# GAME.net
KiCad netlist of a schematic drawn in EAGLE
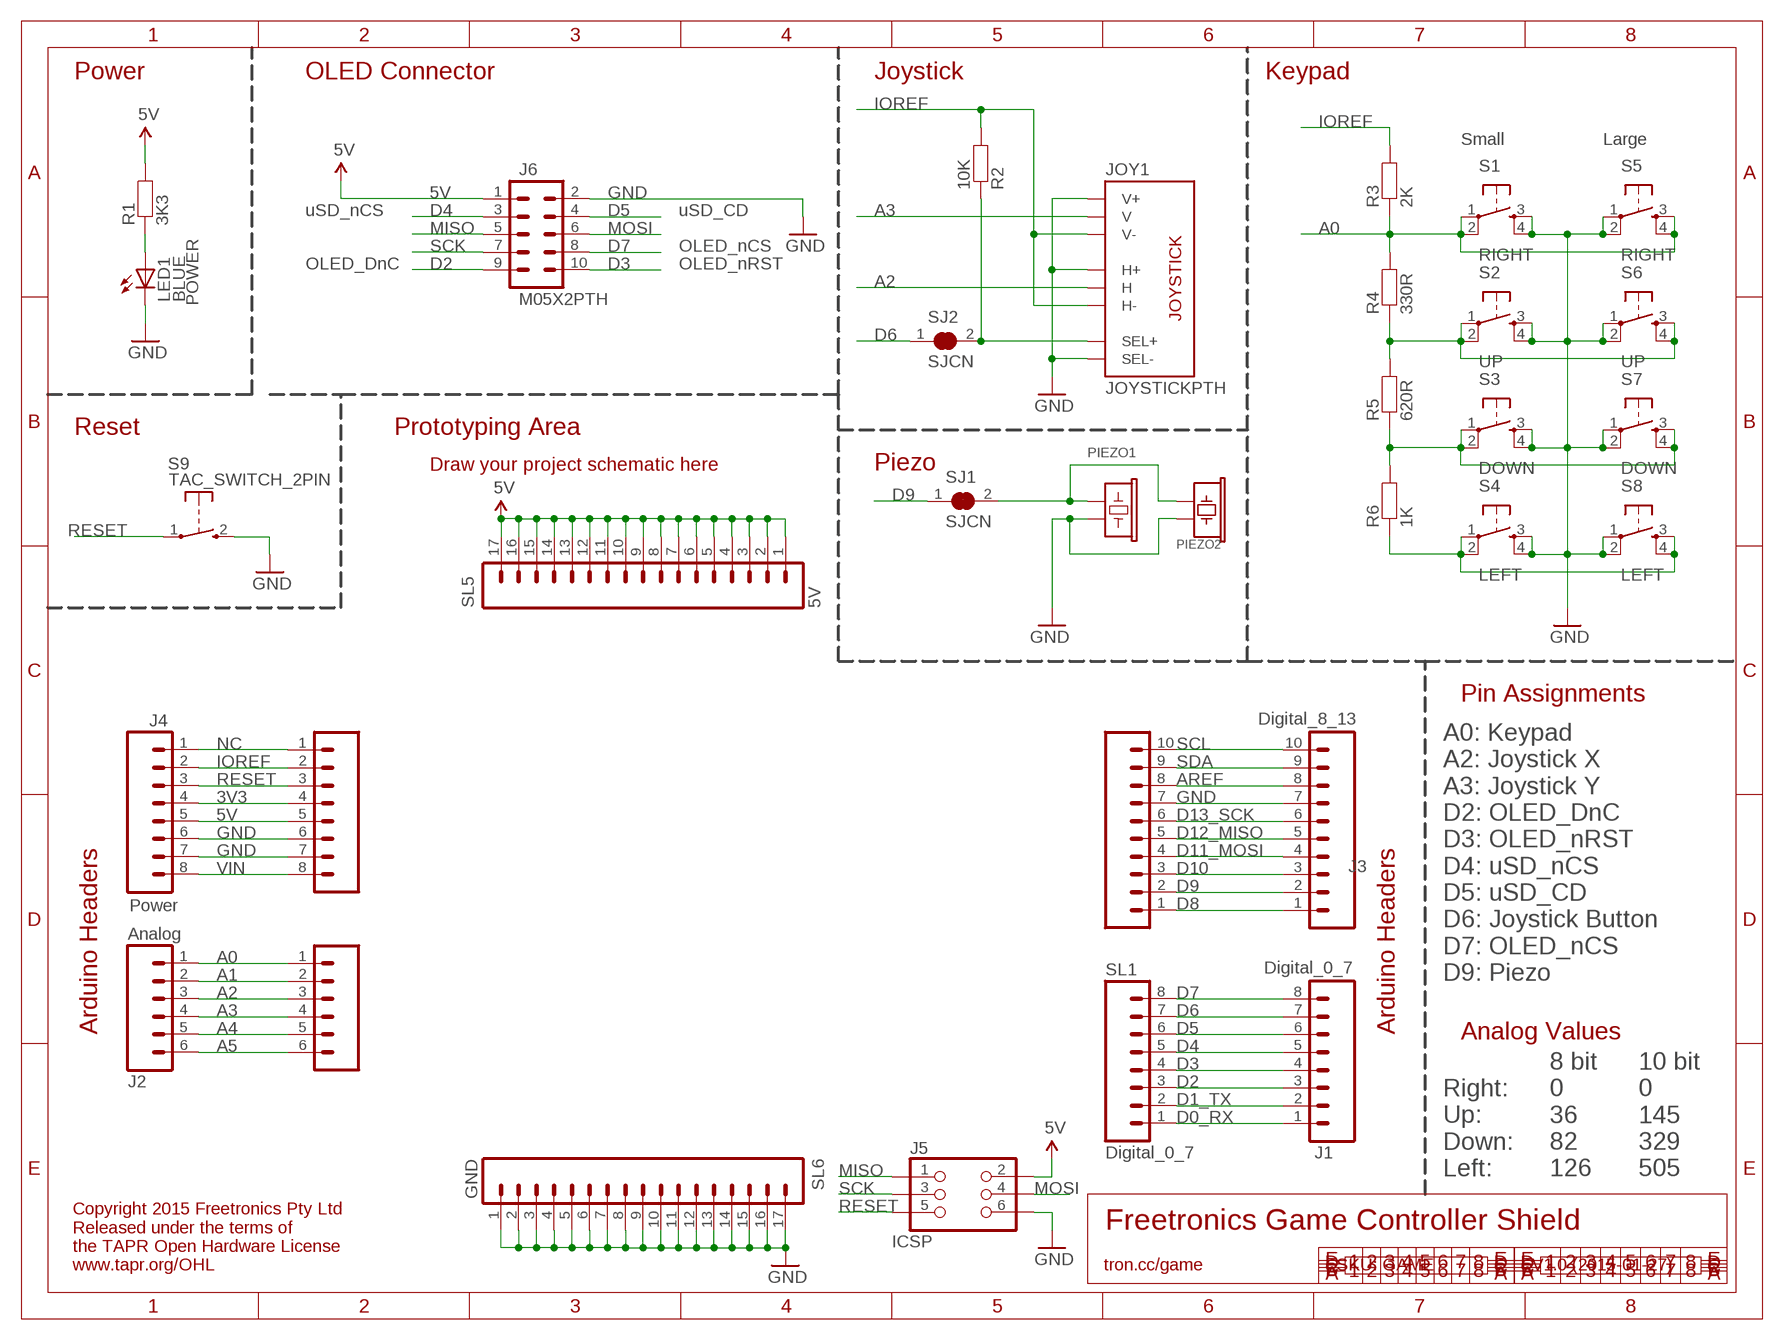
[diagram p0: schematic, sheet 1]

(export (version "E")
  (design (tool "Eeschema 10.0.6"))
  (components
    (comp (ref "J1")
      (value "Digital_0_7")
      (footprint "eagle-import:1X08")
      (libsource (lib "eagle-import") (part "M08"))
    )
    (comp (ref "J2")
      (value "Analog")
      (footprint "eagle-import:1X06")
      (libsource (lib "eagle-import") (part "M06SIP"))
    )
    (comp (ref "J3")
      (value "Digital_8_13")
      (footprint "eagle-import:1X10")
      (libsource (lib "eagle-import") (part "M100.1"))
    )
    (comp (ref "J4")
      (value "Power")
      (footprint "eagle-import:1X08")
      (libsource (lib "eagle-import") (part "M08"))
    )
    (comp (ref "J5")
      (value "ICSP")
      (footprint "eagle-import:2X03PTH")
      (libsource (lib "eagle-import") (part "ICSPPTH"))
    )
    (comp (ref "J6")
      (value "M05X2PTH")
      (footprint "eagle-import:AVR_ICSP")
      (libsource (lib "eagle-import") (part "M05X2PTH"))
    )
    (comp (ref "JOY1")
      (value "JOYSTICKPTH")
      (footprint "eagle-import:JOYSTICK")
      (libsource (lib "eagle-import") (part "JOYSTICKPTH"))
    )
    (comp (ref "LED1")
      (value "BLUE")
      (footprint "eagle-import:LED-0603")
      (libsource (lib "eagle-import") (part "LED0603"))
    )
    (comp (ref "PIEZO1")
      (value "BUZZERSMD12X12")
      (footprint "eagle-import:BUZZER-12X12-SMT")
      (libsource (lib "eagle-import") (part "BUZZERSMD12X12"))
    )
    (comp (ref "PIEZO2")
      (value "PIEZO12MM")
      (footprint "eagle-import:PIEZO12MM")
      (libsource (lib "eagle-import") (part "PIEZO12MM"))
    )
    (comp (ref "R1")
      (value "3K3")
      (footprint "eagle-import:0603")
      (libsource (lib "eagle-import") (part "RESISTOR0603"))
    )
    (comp (ref "R2")
      (value "10K")
      (footprint "eagle-import:0603")
      (libsource (lib "eagle-import") (part "RESISTOR0603"))
    )
    (comp (ref "R3")
      (value "2K")
      (footprint "eagle-import:0603")
      (libsource (lib "eagle-import") (part "RESISTOR0603"))
    )
    (comp (ref "R4")
      (value "330R")
      (footprint "eagle-import:0603")
      (libsource (lib "eagle-import") (part "RESISTOR0603"))
    )
    (comp (ref "R5")
      (value "620R")
      (footprint "eagle-import:0603")
      (libsource (lib "eagle-import") (part "RESISTOR0603"))
    )
    (comp (ref "R6")
      (value "1K")
      (footprint "eagle-import:0603")
      (libsource (lib "eagle-import") (part "RESISTOR0603"))
    )
    (comp (ref "S1")
      (value "RIGHT")
      (footprint "eagle-import:TACTILE-PTH")
      (libsource (lib "eagle-import") (part "TAC_SWITCHPTH"))
    )
    (comp (ref "S2")
      (value "UP")
      (footprint "eagle-import:TACTILE-PTH")
      (libsource (lib "eagle-import") (part "TAC_SWITCHPTH"))
    )
    (comp (ref "S3")
      (value "DOWN")
      (footprint "eagle-import:TACTILE-PTH")
      (libsource (lib "eagle-import") (part "TAC_SWITCHPTH"))
    )
    (comp (ref "S4")
      (value "LEFT")
      (footprint "eagle-import:TACTILE-PTH")
      (libsource (lib "eagle-import") (part "TAC_SWITCHPTH"))
    )
    (comp (ref "S5")
      (value "RIGHT")
      (footprint "eagle-import:TACTILE-PTH-12MM")
      (libsource (lib "eagle-import") (part "TAC_SWITCH12"))
    )
    (comp (ref "S6")
      (value "UP")
      (footprint "eagle-import:TACTILE-PTH-12MM")
      (libsource (lib "eagle-import") (part "TAC_SWITCH12"))
    )
    (comp (ref "S7")
      (value "DOWN")
      (footprint "eagle-import:TACTILE-PTH-12MM")
      (libsource (lib "eagle-import") (part "TAC_SWITCH12"))
    )
    (comp (ref "S8")
      (value "LEFT")
      (footprint "eagle-import:TACTILE-PTH-12MM")
      (libsource (lib "eagle-import") (part "TAC_SWITCH12"))
    )
    (comp (ref "S9")
      (value "TAC_SWITCH_2PIN")
      (footprint "eagle-import:TACTILE_SWITCH_SMD_2PIN_TINY")
      (libsource (lib "eagle-import") (part "TAC_SWITCH_2PIN"))
    )
    (comp (ref "SJ1")
      (value "SJCN")
      (footprint "eagle-import:SJC")
      (libsource (lib "eagle-import") (part "SJCN"))
    )
    (comp (ref "SJ2")
      (value "SJCN")
      (footprint "eagle-import:SJC")
      (libsource (lib "eagle-import") (part "SJCN"))
    )
    (comp (ref "SL1")
      (value "Digital_0_7")
      (footprint "eagle-import:1X08")
      (libsource (lib "eagle-import") (part "freetronics-original_M08"))
    )
    (comp (ref "SL2")
      (value "Analog")
      (footprint "eagle-import:1X06")
      (libsource (lib "eagle-import") (part "M06SIP"))
    )
    (comp (ref "SL3")
      (value "Digital_8_13")
      (footprint "eagle-import:1X10")
      (libsource (lib "eagle-import") (part "M100.1"))
    )
    (comp (ref "SL4")
      (value "Power")
      (footprint "eagle-import:1X08")
      (libsource (lib "eagle-import") (part "M08"))
    )
    (comp (ref "SL5")
      (value "5V")
      (footprint "eagle-import:1X17")
      (libsource (lib "eagle-import") (part "M17"))
    )
    (comp (ref "SL6")
      (value "GND")
      (footprint "eagle-import:1X17")
      (libsource (lib "eagle-import") (part "M17"))
    )
  )
  (nets
    (net (code "1") (name "/3V3") (class "Default")
      (node (ref "J4") (pin "4") (pinfunction "4_4") (pintype "passive"))
      (node (ref "SL4") (pin "4") (pinfunction "4_4") (pintype "passive"))
    )
    (net (code "2") (name "/A0") (class "Default")
      (node (ref "J2") (pin "1") (pinfunction "1_1") (pintype "passive"))
      (node (ref "R3") (pin "1") (pinfunction "1_1") (pintype "passive"))
      (node (ref "R4") (pin "2") (pinfunction "2_2") (pintype "passive"))
      (node (ref "S1") (pin "1") (pinfunction "1_1") (pintype "passive"))
      (node (ref "S1") (pin "2") (pinfunction "2_2") (pintype "passive"))
      (node (ref "S5") (pin "3") (pinfunction "3_3") (pintype "passive"))
      (node (ref "S5") (pin "4") (pinfunction "4_4") (pintype "passive"))
      (node (ref "SL2") (pin "1") (pinfunction "1_1") (pintype "passive"))
    )
    (net (code "3") (name "/A1") (class "Default")
      (node (ref "J2") (pin "2") (pinfunction "2_2") (pintype "passive"))
      (node (ref "SL2") (pin "2") (pinfunction "2_2") (pintype "passive"))
    )
    (net (code "4") (name "/A2") (class "Default")
      (node (ref "J2") (pin "3") (pinfunction "3_3") (pintype "passive"))
      (node (ref "JOY1") (pin "H2") (pinfunction "H_H2") (pintype "bidirectional"))
      (node (ref "SL2") (pin "3") (pinfunction "3_3") (pintype "passive"))
    )
    (net (code "5") (name "/A3") (class "Default")
      (node (ref "J2") (pin "4") (pinfunction "4_4") (pintype "passive"))
      (node (ref "JOY1") (pin "V2") (pinfunction "V_V2") (pintype "bidirectional"))
      (node (ref "SL2") (pin "4") (pinfunction "4_4") (pintype "passive"))
    )
    (net (code "6") (name "/A4") (class "Default")
      (node (ref "J2") (pin "5") (pinfunction "5_5") (pintype "passive"))
      (node (ref "SL2") (pin "5") (pinfunction "5_5") (pintype "passive"))
    )
    (net (code "7") (name "/A5") (class "Default")
      (node (ref "J2") (pin "6") (pinfunction "6_6") (pintype "passive"))
      (node (ref "SL2") (pin "6") (pinfunction "6_6") (pintype "passive"))
    )
    (net (code "8") (name "/AREF") (class "Default")
      (node (ref "J3") (pin "8") (pinfunction "8_8") (pintype "passive"))
      (node (ref "SL3") (pin "8") (pinfunction "8_8") (pintype "passive"))
    )
    (net (code "9") (name "/D0_RX") (class "Default")
      (node (ref "J1") (pin "1") (pinfunction "1_1") (pintype "passive"))
      (node (ref "SL1") (pin "1") (pinfunction "1_1") (pintype "passive"))
    )
    (net (code "10") (name "/D1_TX") (class "Default")
      (node (ref "J1") (pin "2") (pinfunction "2_2") (pintype "passive"))
      (node (ref "SL1") (pin "2") (pinfunction "2_2") (pintype "passive"))
    )
    (net (code "11") (name "/D2") (class "Default")
      (node (ref "J1") (pin "3") (pinfunction "3_3") (pintype "passive"))
      (node (ref "J6") (pin "9") (pinfunction "9_9") (pintype "passive"))
      (node (ref "SL1") (pin "3") (pinfunction "3_3") (pintype "passive"))
    )
    (net (code "12") (name "/D3") (class "Default")
      (node (ref "J1") (pin "4") (pinfunction "4_4") (pintype "passive"))
      (node (ref "J6") (pin "10") (pinfunction "10_10") (pintype "passive"))
      (node (ref "SL1") (pin "4") (pinfunction "4_4") (pintype "passive"))
    )
    (net (code "13") (name "/D4") (class "Default")
      (node (ref "J1") (pin "5") (pinfunction "5_5") (pintype "passive"))
      (node (ref "J6") (pin "3") (pinfunction "3_3") (pintype "passive"))
      (node (ref "SL1") (pin "5") (pinfunction "5_5") (pintype "passive"))
    )
    (net (code "14") (name "/D5") (class "Default")
      (node (ref "J1") (pin "6") (pinfunction "6_6") (pintype "passive"))
      (node (ref "J6") (pin "4") (pinfunction "4_4") (pintype "passive"))
      (node (ref "SL1") (pin "6") (pinfunction "6_6") (pintype "passive"))
    )
    (net (code "15") (name "/D6") (class "Default")
      (node (ref "J1") (pin "7") (pinfunction "7_7") (pintype "passive"))
      (node (ref "SJ2") (pin "1") (pinfunction "1_1") (pintype "passive"))
      (node (ref "SL1") (pin "7") (pinfunction "7_7") (pintype "passive"))
    )
    (net (code "16") (name "/D7") (class "Default")
      (node (ref "J1") (pin "8") (pinfunction "8_8") (pintype "passive"))
      (node (ref "J6") (pin "8") (pinfunction "8_8") (pintype "passive"))
      (node (ref "SL1") (pin "8") (pinfunction "8_8") (pintype "passive"))
    )
    (net (code "17") (name "/D8") (class "Default")
      (node (ref "J3") (pin "1") (pinfunction "1_1") (pintype "passive"))
      (node (ref "SL3") (pin "1") (pinfunction "1_1") (pintype "passive"))
    )
    (net (code "18") (name "/D9") (class "Default")
      (node (ref "J3") (pin "2") (pinfunction "2_2") (pintype "passive"))
      (node (ref "SJ1") (pin "1") (pinfunction "1_1") (pintype "passive"))
      (node (ref "SL3") (pin "2") (pinfunction "2_2") (pintype "passive"))
    )
    (net (code "19") (name "/D10") (class "Default")
      (node (ref "J3") (pin "3") (pinfunction "3_3") (pintype "passive"))
      (node (ref "SL3") (pin "3") (pinfunction "3_3") (pintype "passive"))
    )
    (net (code "20") (name "/D11_MOSI") (class "Default")
      (node (ref "J3") (pin "4") (pinfunction "4_4") (pintype "passive"))
      (node (ref "SL3") (pin "4") (pinfunction "4_4") (pintype "passive"))
    )
    (net (code "21") (name "/D12_MISO") (class "Default")
      (node (ref "J3") (pin "5") (pinfunction "5_5") (pintype "passive"))
      (node (ref "SL3") (pin "5") (pinfunction "5_5") (pintype "passive"))
    )
    (net (code "22") (name "/D13_SCK") (class "Default")
      (node (ref "J3") (pin "6") (pinfunction "6_6") (pintype "passive"))
      (node (ref "SL3") (pin "6") (pinfunction "6_6") (pintype "passive"))
    )
    (net (code "23") (name "/IOREF") (class "Default")
      (node (ref "J4") (pin "2") (pinfunction "2_2") (pintype "passive"))
      (node (ref "JOY1") (pin "H3") (pinfunction "H-_H3") (pintype "bidirectional"))
      (node (ref "JOY1") (pin "V3") (pinfunction "V-_V3") (pintype "bidirectional"))
      (node (ref "R2") (pin "2") (pinfunction "2_2") (pintype "passive"))
      (node (ref "R3") (pin "2") (pinfunction "2_2") (pintype "passive"))
      (node (ref "SL4") (pin "2") (pinfunction "2_2") (pintype "passive"))
    )
    (net (code "24") (name "/MISO") (class "Default")
      (node (ref "J5") (pin "1") (pinfunction "1_1") (pintype "passive"))
      (node (ref "J6") (pin "5") (pinfunction "5_5") (pintype "passive"))
    )
    (net (code "25") (name "/MOSI") (class "Default")
      (node (ref "J5") (pin "4") (pinfunction "4_4") (pintype "passive"))
      (node (ref "J6") (pin "6") (pinfunction "6_6") (pintype "passive"))
    )
    (net (code "26") (name "/NC") (class "Default")
      (node (ref "J4") (pin "1") (pinfunction "1_1") (pintype "passive"))
      (node (ref "SL4") (pin "1") (pinfunction "1_1") (pintype "passive"))
    )
    (net (code "27") (name "/RESET") (class "Default")
      (node (ref "J4") (pin "3") (pinfunction "3_3") (pintype "passive"))
      (node (ref "J5") (pin "5") (pinfunction "5_5") (pintype "passive"))
      (node (ref "S9") (pin "1") (pinfunction "P_1") (pintype "passive"))
      (node (ref "SL4") (pin "3") (pinfunction "3_3") (pintype "passive"))
    )
    (net (code "28") (name "/SCK") (class "Default")
      (node (ref "J5") (pin "3") (pinfunction "3_3") (pintype "passive"))
      (node (ref "J6") (pin "7") (pinfunction "7_7") (pintype "passive"))
    )
    (net (code "29") (name "/SCL") (class "Default")
      (node (ref "J3") (pin "10") (pinfunction "10_10") (pintype "passive"))
      (node (ref "SL3") (pin "10") (pinfunction "10_10") (pintype "passive"))
    )
    (net (code "30") (name "/SDA") (class "Default")
      (node (ref "J3") (pin "9") (pinfunction "9_9") (pintype "passive"))
      (node (ref "SL3") (pin "9") (pinfunction "9_9") (pintype "passive"))
    )
    (net (code "31") (name "/VIN") (class "Default")
      (node (ref "J4") (pin "8") (pinfunction "8_8") (pintype "passive"))
      (node (ref "SL4") (pin "8") (pinfunction "8_8") (pintype "passive"))
    )
    (net (code "32") (name "5V") (class "Default")
      (node (ref "J4") (pin "5") (pinfunction "5_5") (pintype "passive"))
      (node (ref "J5") (pin "2") (pinfunction "2_2") (pintype "passive"))
      (node (ref "J6") (pin "1") (pinfunction "1_1") (pintype "passive"))
      (node (ref "R1") (pin "2") (pinfunction "2_2") (pintype "passive"))
      (node (ref "SL4") (pin "5") (pinfunction "5_5") (pintype "passive"))
      (node (ref "SL5") (pin "1") (pinfunction "1_1") (pintype "passive"))
      (node (ref "SL5") (pin "10") (pinfunction "10_10") (pintype "passive"))
      (node (ref "SL5") (pin "11") (pinfunction "11_11") (pintype "passive"))
      (node (ref "SL5") (pin "12") (pinfunction "12_12") (pintype "passive"))
      (node (ref "SL5") (pin "13") (pinfunction "13_13") (pintype "passive"))
      (node (ref "SL5") (pin "14") (pinfunction "14_14") (pintype "passive"))
      (node (ref "SL5") (pin "15") (pinfunction "15_15") (pintype "passive"))
      (node (ref "SL5") (pin "16") (pinfunction "16_16") (pintype "passive"))
      (node (ref "SL5") (pin "17") (pinfunction "17_17") (pintype "passive"))
      (node (ref "SL5") (pin "2") (pinfunction "2_2") (pintype "passive"))
      (node (ref "SL5") (pin "3") (pinfunction "3_3") (pintype "passive"))
      (node (ref "SL5") (pin "4") (pinfunction "4_4") (pintype "passive"))
      (node (ref "SL5") (pin "5") (pinfunction "5_5") (pintype "passive"))
      (node (ref "SL5") (pin "6") (pinfunction "6_6") (pintype "passive"))
      (node (ref "SL5") (pin "7") (pinfunction "7_7") (pintype "passive"))
      (node (ref "SL5") (pin "8") (pinfunction "8_8") (pintype "passive"))
      (node (ref "SL5") (pin "9") (pinfunction "9_9") (pintype "passive"))
    )
    (net (code "33") (name "GND") (class "Default")
      (node (ref "J3") (pin "7") (pinfunction "7_7") (pintype "passive"))
      (node (ref "J4") (pin "6") (pinfunction "6_6") (pintype "passive"))
      (node (ref "J4") (pin "7") (pinfunction "7_7") (pintype "passive"))
      (node (ref "J5") (pin "6") (pinfunction "6_6") (pintype "passive"))
      (node (ref "J6") (pin "2") (pinfunction "2_2") (pintype "passive"))
      (node (ref "JOY1") (pin "B2A") (pinfunction "SEL-_B2A") (pintype "bidirectional"))
      (node (ref "JOY1") (pin "H1") (pinfunction "H+_H1") (pintype "bidirectional"))
      (node (ref "JOY1") (pin "V1") (pinfunction "V+_V1") (pintype "bidirectional"))
      (node (ref "LED1") (pin "C") (pinfunction "C_C") (pintype "passive"))
      (node (ref "PIEZO1") (pin "1") (pinfunction "1_1") (pintype "passive"))
      (node (ref "PIEZO2") (pin "2") (pinfunction "2_2") (pintype "bidirectional"))
      (node (ref "S1") (pin "3") (pinfunction "3_3") (pintype "passive"))
      (node (ref "S1") (pin "4") (pinfunction "4_4") (pintype "passive"))
      (node (ref "S2") (pin "3") (pinfunction "3_3") (pintype "passive"))
      (node (ref "S2") (pin "4") (pinfunction "4_4") (pintype "passive"))
      (node (ref "S3") (pin "3") (pinfunction "3_3") (pintype "passive"))
      (node (ref "S3") (pin "4") (pinfunction "4_4") (pintype "passive"))
      (node (ref "S4") (pin "3") (pinfunction "3_3") (pintype "passive"))
      (node (ref "S4") (pin "4") (pinfunction "4_4") (pintype "passive"))
      (node (ref "S5") (pin "1") (pinfunction "1_1") (pintype "passive"))
      (node (ref "S5") (pin "2") (pinfunction "2_2") (pintype "passive"))
      (node (ref "S6") (pin "1") (pinfunction "1_1") (pintype "passive"))
      (node (ref "S6") (pin "2") (pinfunction "2_2") (pintype "passive"))
      (node (ref "S7") (pin "1") (pinfunction "1_1") (pintype "passive"))
      (node (ref "S7") (pin "2") (pinfunction "2_2") (pintype "passive"))
      (node (ref "S8") (pin "1") (pinfunction "1_1") (pintype "passive"))
      (node (ref "S8") (pin "2") (pinfunction "2_2") (pintype "passive"))
      (node (ref "S9") (pin "2") (pinfunction "S_2") (pintype "passive"))
      (node (ref "SL3") (pin "7") (pinfunction "7_7") (pintype "passive"))
      (node (ref "SL4") (pin "6") (pinfunction "6_6") (pintype "passive"))
      (node (ref "SL4") (pin "7") (pinfunction "7_7") (pintype "passive"))
      (node (ref "SL6") (pin "1") (pinfunction "1_1") (pintype "passive"))
      (node (ref "SL6") (pin "10") (pinfunction "10_10") (pintype "passive"))
      (node (ref "SL6") (pin "11") (pinfunction "11_11") (pintype "passive"))
      (node (ref "SL6") (pin "12") (pinfunction "12_12") (pintype "passive"))
      (node (ref "SL6") (pin "13") (pinfunction "13_13") (pintype "passive"))
      (node (ref "SL6") (pin "14") (pinfunction "14_14") (pintype "passive"))
      (node (ref "SL6") (pin "15") (pinfunction "15_15") (pintype "passive"))
      (node (ref "SL6") (pin "16") (pinfunction "16_16") (pintype "passive"))
      (node (ref "SL6") (pin "17") (pinfunction "17_17") (pintype "passive"))
      (node (ref "SL6") (pin "2") (pinfunction "2_2") (pintype "passive"))
      (node (ref "SL6") (pin "3") (pinfunction "3_3") (pintype "passive"))
      (node (ref "SL6") (pin "4") (pinfunction "4_4") (pintype "passive"))
      (node (ref "SL6") (pin "5") (pinfunction "5_5") (pintype "passive"))
      (node (ref "SL6") (pin "6") (pinfunction "6_6") (pintype "passive"))
      (node (ref "SL6") (pin "7") (pinfunction "7_7") (pintype "passive"))
      (node (ref "SL6") (pin "8") (pinfunction "8_8") (pintype "passive"))
      (node (ref "SL6") (pin "9") (pinfunction "9_9") (pintype "passive"))
    )
    (net (code "34") (name "Net-(JOY1-SEL+)") (class "Default")
      (node (ref "JOY1") (pin "B1A") (pinfunction "SEL+_B1A") (pintype "bidirectional"))
      (node (ref "R2") (pin "1") (pinfunction "1_1") (pintype "passive"))
      (node (ref "SJ2") (pin "2") (pinfunction "2_2") (pintype "passive"))
    )
    (net (code "35") (name "Net-(LED1-PadA)") (class "Default")
      (node (ref "LED1") (pin "A") (pinfunction "A_A") (pintype "passive"))
      (node (ref "R1") (pin "1") (pinfunction "1_1") (pintype "passive"))
    )
    (net (code "36") (name "Net-(PIEZO1-Pad2)") (class "Default")
      (node (ref "PIEZO1") (pin "2") (pinfunction "2_2") (pintype "passive"))
      (node (ref "PIEZO2") (pin "1") (pinfunction "1_1") (pintype "bidirectional"))
      (node (ref "SJ1") (pin "2") (pinfunction "2_2") (pintype "passive"))
    )
    (net (code "37") (name "Net-(R4-Pad1)") (class "Default")
      (node (ref "R4") (pin "1") (pinfunction "1_1") (pintype "passive"))
      (node (ref "R5") (pin "2") (pinfunction "2_2") (pintype "passive"))
      (node (ref "S2") (pin "1") (pinfunction "1_1") (pintype "passive"))
      (node (ref "S2") (pin "2") (pinfunction "2_2") (pintype "passive"))
      (node (ref "S6") (pin "3") (pinfunction "3_3") (pintype "passive"))
      (node (ref "S6") (pin "4") (pinfunction "4_4") (pintype "passive"))
    )
    (net (code "38") (name "Net-(R5-Pad1)") (class "Default")
      (node (ref "R5") (pin "1") (pinfunction "1_1") (pintype "passive"))
      (node (ref "R6") (pin "2") (pinfunction "2_2") (pintype "passive"))
      (node (ref "S3") (pin "1") (pinfunction "1_1") (pintype "passive"))
      (node (ref "S3") (pin "2") (pinfunction "2_2") (pintype "passive"))
      (node (ref "S7") (pin "3") (pinfunction "3_3") (pintype "passive"))
      (node (ref "S7") (pin "4") (pinfunction "4_4") (pintype "passive"))
    )
    (net (code "39") (name "Net-(R6-Pad1)") (class "Default")
      (node (ref "R6") (pin "1") (pinfunction "1_1") (pintype "passive"))
      (node (ref "S4") (pin "1") (pinfunction "1_1") (pintype "passive"))
      (node (ref "S4") (pin "2") (pinfunction "2_2") (pintype "passive"))
      (node (ref "S8") (pin "3") (pinfunction "3_3") (pintype "passive"))
      (node (ref "S8") (pin "4") (pinfunction "4_4") (pintype "passive"))
    )
  )
)
